# 12V_Power_Supply.net
KiCad netlist of a schematic drawn in Altium Designer
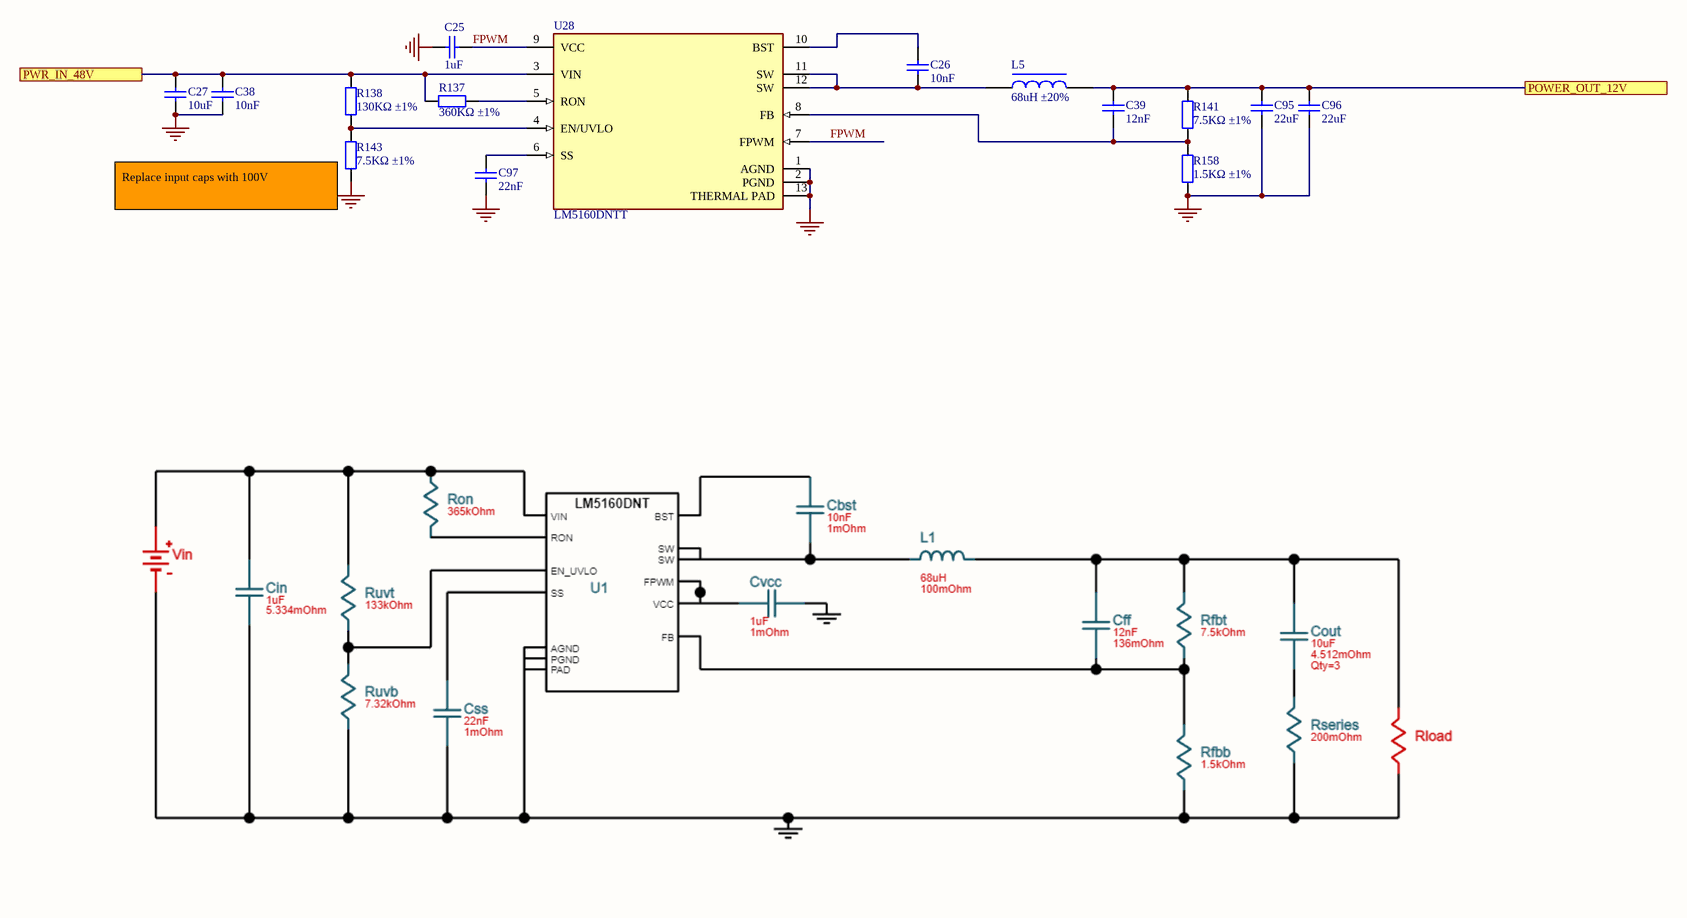
[diagram p0: 12V_Power_Supply.SchDoc]

(export (version "E")
  (design (tool "Eeschema 10.0.6"))
  (components
    (comp (ref "C25")
      (value "1uF")
      (footprint "0603_C")
      (description "Chip capacitors")
      (fields
        (field (name "MANUFACTURER") "Samsung Electro-Mechanics")
        (field (name "PARTNUMBER") "CL10A105KB8NNNC")
      )
      (libsource (lib "Cap") (part "0603 1uF (105) 10% 50V"))
    )
    (comp (ref "C26")
      (value "10nF")
      (footprint "0603_C")
      (description "Chip capacitors")
      (fields
        (field (name "MANUFACTURER") "Guangdong Fenghua Advanced Tech")
        (field (name "PARTNUMBER") "0603B103K500NT")
      )
      (libsource (lib "Cap") (part "0603 10nF (103) 10% 50V"))
    )
    (comp (ref "C27")
      (value "10uF")
      (footprint "1206_C")
      (description "Chip capacitors")
      (fields
        (field (name "MANUFACTURER") "Samsung Electro-Mechanics")
        (field (name "PARTNUMBER") "CL31A106KBHNNNE")
      )
      (libsource (lib "Cap") (part "1206 10uF (106) 10% 50V"))
    )
    (comp (ref "C38")
      (value "10nF")
      (footprint "0603_C")
      (description "Chip capacitors")
      (fields
        (field (name "MANUFACTURER") "Guangdong Fenghua Advanced Tech")
        (field (name "PARTNUMBER") "0603B103K500NT")
      )
      (libsource (lib "Cap") (part "0603 10nF (103) 10% 50V"))
    )
    (comp (ref "C39")
      (value "12nF")
      (footprint "0603_C")
      (description "Chip capacitors")
      (fields
        (field (name "MANUFACTURER") "Guangdong Fenghua Advanced Tech")
        (field (name "PARTNUMBER") "0603B123K500NT")
      )
      (libsource (lib "Cap") (part "0603 12nF (123) 10% 50V"))
    )
    (comp (ref "C95")
      (value "22uF")
      (footprint "0805_C")
      (description "Chip capacitors")
      (fields
        (field (name "MANUFACTURER") "Samsung Electro-Mechanics")
        (field (name "PARTNUMBER") "CL21A226MAQNNNE")
      )
      (libsource (lib "Cap") (part "0805 22uF (226) 20% 25V"))
    )
    (comp (ref "C96")
      (value "22uF")
      (footprint "0805_C")
      (description "Chip capacitors")
      (fields
        (field (name "MANUFACTURER") "Samsung Electro-Mechanics")
        (field (name "PARTNUMBER") "CL21A226MAQNNNE")
      )
      (libsource (lib "Cap") (part "0805 22uF (226) 20% 25V"))
    )
    (comp (ref "C97")
      (value "22nF")
      (footprint "0603_C")
      (description "Chip capacitors")
      (fields
        (field (name "MANUFACTURER") "Samsung Electro-Mechanics")
        (field (name "PARTNUMBER") "CL10B223KB8NNNC")
      )
      (libsource (lib "Cap") (part "0603 22nF (223) 10% 50V"))
    )
    (comp (ref "L5")
      (value "68uH ±20%")
      (footprint "INDP126126X68N")
      (description "2A 68uH ±20% SMD,12.5x12.5mm Power Inductors ROHS")
      (libsource (lib "IUD") (part "12.5x12.5x6.5 68uH 20%"))
    )
    (comp (ref "R137")
      (value "360KΩ ±1%")
      (footprint "0603_R")
      (description "Chip resistor")
      (fields (field (name "MANUFACTURER") "Uniroyal Elec") (field (name "PARTNUMBER") "0603WAF3603T5E"))
      (libsource (lib "RES") (part "0603 360K (3603) 1%"))
    )
    (comp (ref "R138")
      (value "130KΩ ±1%")
      (footprint "0603_R")
      (description "Chip resistor")
      (fields (field (name "MANUFACTURER") "Uniroyal Elec") (field (name "PARTNUMBER") "0603WAF1303T5E"))
      (libsource (lib "RES") (part "0603 130K (1303) 1%"))
    )
    (comp (ref "R141")
      (value "7.5KΩ ±1%")
      (footprint "0603_R")
      (description "Chip resistor")
      (fields (field (name "MANUFACTURER") "Uniroyal Elec") (field (name "PARTNUMBER") "0603WAF7501T5E"))
      (libsource (lib "RES") (part "0603 7.5K (7501) 1%"))
    )
    (comp (ref "R143")
      (value "7.5KΩ ±1%")
      (footprint "0603_R")
      (description "Chip resistor")
      (fields (field (name "MANUFACTURER") "Uniroyal Elec") (field (name "PARTNUMBER") "0603WAF7501T5E"))
      (libsource (lib "RES") (part "0603 7.5K (7501) 1%"))
    )
    (comp (ref "R158")
      (value "1.5KΩ ±1%")
      (footprint "0603_R")
      (description "Chip resistor")
      (fields (field (name "MANUFACTURER") "Uniroyal Elec") (field (name "PARTNUMBER") "0603WAF1501T5E"))
      (libsource (lib "RES") (part "0603 1.5K (1501) 1%"))
    )
    (comp (ref "U28")
      (value "LM5160DNTT")
      (footprint "FP-DNT0012B-MFG")
      (description "IC REG BCK FLYBCK ADJ 12WSON")
      (libsource (lib "Altium Content Vault") (part "1d7f67e77d13906a14c82768b36e50a"))
    )
  )
  (nets
    (net (code "1") (name "/FPWM") (class "Default")
      (node (ref "C25") (pin "2") (pinfunction "2_2") (pintype "passive"))
      (node (ref "U28") (pin "7") (pinfunction "FPWM_7") (pintype "input"))
      (node (ref "U28") (pin "9") (pinfunction "VCC_9") (pintype "power_in"))
    )
    (net (code "2") (name "/POWER_OUT_12V") (class "Default")
      (node (ref "C39") (pin "2") (pinfunction "2_2") (pintype "passive"))
      (node (ref "C95") (pin "2") (pinfunction "2_2") (pintype "passive"))
      (node (ref "C96") (pin "2") (pinfunction "2_2") (pintype "passive"))
      (node (ref "L5") (pin "2") (pinfunction "2_2") (pintype "passive"))
      (node (ref "R141") (pin "2") (pinfunction "2_2") (pintype "passive"))
    )
    (net (code "3") (name "/PWR_IN_48V") (class "Default")
      (node (ref "C27") (pin "2") (pinfunction "2_2") (pintype "passive"))
      (node (ref "C38") (pin "2") (pinfunction "2_2") (pintype "passive"))
      (node (ref "R137") (pin "1") (pinfunction "1_1") (pintype "passive"))
      (node (ref "R138") (pin "2") (pinfunction "2_2") (pintype "passive"))
      (node (ref "U28") (pin "3") (pinfunction "VIN_3") (pintype "power_in"))
    )
    (net (code "4") (name "GND") (class "Default")
      (node (ref "C25") (pin "1") (pinfunction "1_1") (pintype "passive"))
      (node (ref "C27") (pin "1") (pinfunction "1_1") (pintype "passive"))
      (node (ref "C38") (pin "1") (pinfunction "1_1") (pintype "passive"))
      (node (ref "C95") (pin "1") (pinfunction "1_1") (pintype "passive"))
      (node (ref "C96") (pin "1") (pinfunction "1_1") (pintype "passive"))
      (node (ref "C97") (pin "1") (pinfunction "1_1") (pintype "passive"))
      (node (ref "R143") (pin "1") (pinfunction "1_1") (pintype "passive"))
      (node (ref "R158") (pin "1") (pinfunction "1_1") (pintype "passive"))
      (node (ref "U28") (pin "1") (pinfunction "AGND_1") (pintype "power_in"))
      (node (ref "U28") (pin "13") (pinfunction "THERMAL_PAD_13") (pintype "power_in"))
      (node (ref "U28") (pin "2") (pinfunction "PGND_2") (pintype "power_in"))
    )
    (net (code "5") (name "Net-(C26-Pad2)") (class "Default")
      (node (ref "C26") (pin "2") (pinfunction "2_2") (pintype "passive"))
      (node (ref "L5") (pin "1") (pinfunction "1_1") (pintype "passive"))
      (node (ref "U28") (pin "11") (pinfunction "SW_11") (pintype "passive"))
      (node (ref "U28") (pin "12") (pinfunction "SW_12") (pintype "passive"))
    )
    (net (code "6") (name "Net-(U28-BST)") (class "Default")
      (node (ref "C26") (pin "1") (pinfunction "1_1") (pintype "passive"))
      (node (ref "U28") (pin "10") (pinfunction "BST_10") (pintype "passive"))
    )
    (net (code "7") (name "Net-(U28-EN{slash}UVLO)") (class "Default")
      (node (ref "R138") (pin "1") (pinfunction "1_1") (pintype "passive"))
      (node (ref "R143") (pin "2") (pinfunction "2_2") (pintype "passive"))
      (node (ref "U28") (pin "4") (pinfunction "EN/UVLO_4") (pintype "input"))
    )
    (net (code "8") (name "Net-(U28-FB)") (class "Default")
      (node (ref "C39") (pin "1") (pinfunction "1_1") (pintype "passive"))
      (node (ref "R141") (pin "1") (pinfunction "1_1") (pintype "passive"))
      (node (ref "R158") (pin "2") (pinfunction "2_2") (pintype "passive"))
      (node (ref "U28") (pin "8") (pinfunction "FB_8") (pintype "input"))
    )
    (net (code "9") (name "Net-(U28-RON)") (class "Default")
      (node (ref "R137") (pin "2") (pinfunction "2_2") (pintype "passive"))
      (node (ref "U28") (pin "5") (pinfunction "RON_5") (pintype "input"))
    )
    (net (code "10") (name "Net-(U28-SS)") (class "Default")
      (node (ref "C97") (pin "2") (pinfunction "2_2") (pintype "passive"))
      (node (ref "U28") (pin "6") (pinfunction "SS_6") (pintype "input"))
    )
  )
)
